# Charging.net
KiCad netlist of a schematic drawn in Altium Designer
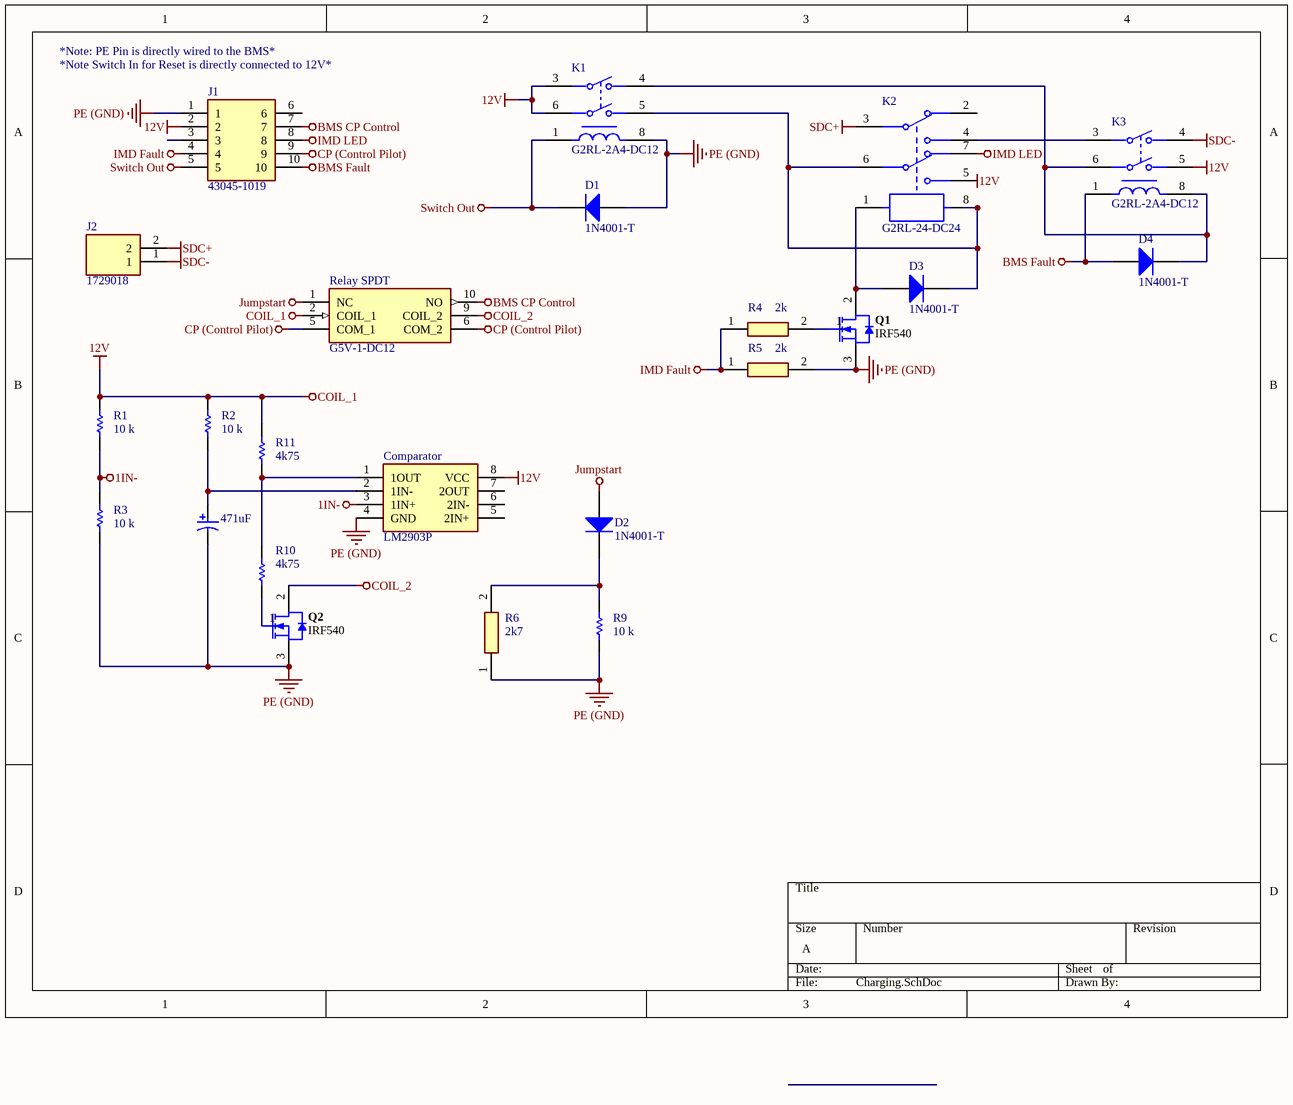
[diagram p0: Charging.SchDoc]

(export (version "E")
  (design (tool "Eeschema 10.0.6"))
  (components
    (comp (ref "471uF")
      (value "ECA-1JHG471")
      (footprint "CAPPR65-500-2000X1250X2200")
      (fields (field (name "MANUFACTURER") "Panasonic"))
      (libsource (lib "Altium Content Vault") (part "CAP-P-2"))
    )
    (comp (ref "Comparator")
      (value "LM2903P")
      (footprint "SamacSys:DIP794W53P254L959H508Q8N")
      (description "Integrated Circuit")
      (fields (field (name "MOUSER PART NUMBER") "595-LM2903P"))
      (libsource (lib "*") (part "LM2903P"))
    )
    (comp (ref "D1")
      (value "1N4001-T")
      (footprint "DIOD-DO-41-P-2_V")
      (description "1.0 A Rectifier, 15 pF, 50 V, -65 to 150 degC, 2-Pin DO-41 Plastic, RoHS, Tape and Reel")
      (fields (field (name "MANUFACTURER") "Diodes Inc"))
      (libsource (lib "Altium Content Vault") (part "DIOD-D-A1K2-2"))
    )
    (comp (ref "D2")
      (value "1N4001-T")
      (footprint "DIOD-DO-41-P-2_V")
      (description "1.0 A Rectifier, 15 pF, 50 V, -65 to 150 degC, 2-Pin DO-41 Plastic, RoHS, Tape and Reel")
      (fields (field (name "MANUFACTURER") "Diodes Inc"))
      (libsource (lib "Altium Content Vault") (part "DIOD-D-A1K2-2"))
    )
    (comp (ref "D3")
      (value "1N4001-T")
      (footprint "DIOD-DO-41-P-2_V")
      (description "1.0 A Rectifier, 15 pF, 50 V, -65 to 150 degC, 2-Pin DO-41 Plastic, RoHS, Tape and Reel")
      (fields (field (name "MANUFACTURER") "Diodes Inc"))
      (libsource (lib "Altium Content Vault") (part "DIOD-D-A1K2-2"))
    )
    (comp (ref "D4")
      (value "1N4001-T")
      (footprint "DIOD-DO-41-P-2_V")
      (description "1.0 A Rectifier, 15 pF, 50 V, -65 to 150 degC, 2-Pin DO-41 Plastic, RoHS, Tape and Reel")
      (fields (field (name "MANUFACTURER") "Diodes Inc"))
      (libsource (lib "Altium Content Vault") (part "DIOD-D-A1K2-2"))
    )
    (comp (ref "J1")
      (value "43045-1019")
      (footprint "SamacSys:43045-10YY_181920")
      (description "Connector")
      (fields (field (name "MOUSER PART NUMBER") "538-43045-1019"))
      (libsource (lib "*") (part "43045-1019"))
    )
    (comp (ref "J2")
      (value "1729018")
      (footprint "SamacSys:1729018")
      (description "Connector")
      (fields (field (name "MOUSER PART NUMBER") "651-1729018"))
      (libsource (lib "*") (part "1729018"))
    )
    (comp (ref "K1")
      (value "G2RL-2A4-DC12")
      (footprint "FP-G2RL-2A4-DC12-MFG")
      (description "RELAY GEN PURPOSE DPST 8A 12V")
      (libsource (lib "Altium Content Vault") (part "dfb52caf01785165d8ace8a37fe0b79"))
    )
    (comp (ref "K2")
      (value "G2RL-24-DC24")
      (footprint "OMRON-G2RL-24_V")
      (fields (field (name "MANUFACTURER") "Omron"))
      (libsource (lib "Altium Content Vault") (part "RELAY-DPDT-8_C"))
    )
    (comp (ref "K3")
      (value "G2RL-2A4-DC12")
      (footprint "FP-G2RL-2A4-DC12-MFG")
      (description "RELAY GEN PURPOSE DPST 8A 12V")
      (libsource (lib "Altium Content Vault") (part "dfb52caf01785165d8ace8a37fe0b79"))
    )
    (comp (ref "Q1")
      (value "IRF540")
      (footprint "VISH-TO-220AB-3_A")
      (description "Power MOSFET, 100 VDS, -55 to 175 degC, 3-Pin TO-220AB, RoHS, Tube")
      (fields (field (name "MANUFACTURER") "Vishay"))
      (libsource (lib "Altium Content Vault") (part "NEMOS-GDS-3"))
    )
    (comp (ref "Q2")
      (value "IRF540")
      (footprint "VISH-TO-220AB-3_A")
      (description "Power MOSFET, 100 VDS, -55 to 175 degC, 3-Pin TO-220AB, RoHS, Tube")
      (fields (field (name "MANUFACTURER") "Vishay"))
      (libsource (lib "Altium Content Vault") (part "NEMOS-GDS-3"))
    )
    (comp (ref "R1")
      (value "MFR-25FBF52-1K")
      (footprint "RESA60-630X240")
      (description "Axial Resistor, 1 KOhm, +/- 1%, 250 mW, -55 to 155 degC, 2-Pin THD, RoHS, Bulk")
      (fields (field (name "TOLERANCE") "1%") (field (name "RESISTANCE") "10 k"))
      (libsource (lib "Altium Content Vault") (part "RES-2"))
    )
    (comp (ref "R2")
      (value "MFR-25FBF52-1K")
      (footprint "RESA60-630X240")
      (description "Axial Resistor, 1 KOhm, +/- 1%, 250 mW, -55 to 155 degC, 2-Pin THD, RoHS, Bulk")
      (fields (field (name "TOLERANCE") "1%") (field (name "RESISTANCE") "10 k"))
      (libsource (lib "Altium Content Vault") (part "RES-2"))
    )
    (comp (ref "R3")
      (value "MFR-25FBF52-1K")
      (footprint "RESA60-630X240")
      (description "Axial Resistor, 1 KOhm, +/- 1%, 250 mW, -55 to 155 degC, 2-Pin THD, RoHS, Bulk")
      (fields (field (name "TOLERANCE") "1%") (field (name "RESISTANCE") "10 k"))
      (libsource (lib "Altium Content Vault") (part "RES-2"))
    )
    (comp (ref "R4")
      (value "MFR-25FBF52-2K")
      (footprint "SamacSys:RESAD1590W60L630D240")
      (description "Resistor")
      (fields (field (name "RESISTANCE") "2k"))
      (libsource (lib "*") (part "MFR-25FBF52-2K"))
    )
    (comp (ref "R5")
      (value "MFR-25FBF52-2K")
      (footprint "SamacSys:RESAD1590W60L630D240")
      (description "Resistor")
      (fields (field (name "RESISTANCE") "2k"))
      (libsource (lib "*") (part "MFR-25FBF52-2K"))
    )
    (comp (ref "R6")
      (value "2.7k")
      (footprint "SamacSys:RESAD1590W60L630D240")
      (description "Resistor")
      (fields
        (field (name "MANUFACTURER_PART_NUMBER") "CFR-25JB-52-2K7")
        (field (name "MOUSER PART NUMBER") "603-CFR-25JB-52-2K7")
        (field (name "RESISTANCE") "2k7")
      )
      (libsource (lib "*") (part "CFR-25JB-52-2K7"))
    )
    (comp (ref "R9")
      (value "MFR-25FBF52-1K")
      (footprint "RESA60-630X240")
      (description "Axial Resistor, 1 KOhm, +/- 1%, 250 mW, -55 to 155 degC, 2-Pin THD, RoHS, Bulk")
      (fields (field (name "TOLERANCE") "1%") (field (name "RESISTANCE") "10 k"))
      (libsource (lib "Altium Content Vault") (part "RES-2"))
    )
    (comp (ref "R10")
      (value "4.75 k")
      (footprint "RESA60-630X240")
      (description "Axial Resistor, 4.75 KOhm, +/- 1%, 0.25 W, -55 to 155 degC, 2-Pin THD, RoHS, Bulk")
      (fields (field (name "TOLERANCE") "10%") (field (name "RESISTANCE") "4k75"))
      (libsource (lib "Altium Content Vault") (part "RES-2"))
    )
    (comp (ref "R11")
      (value "4.75 k")
      (footprint "RESA60-630X240")
      (description "Axial Resistor, 4.75 KOhm, +/- 1%, 0.25 W, -55 to 155 degC, 2-Pin THD, RoHS, Bulk")
      (fields (field (name "TOLERANCE") "10%") (field (name "RESISTANCE") "4k75"))
      (libsource (lib "Altium Content Vault") (part "RES-2"))
    )
    (comp (ref "Relay SPDT")
      (value "G5V-1-DC12")
      (footprint "SamacSys:G5V1DC12")
      (description "Relay or Contactor")
      (fields (field (name "MOUSER PART NUMBER") "653-G5V-1-DC12"))
      (libsource (lib "*") (part "G5V-1-DC12"))
    )
  )
  (nets
    (net (code "1") (name "1IN-") (class "Default")
      (node (ref "Comparator") (pin "3") (pinfunction "1IN+_3") (pintype "passive"))
      (node (ref "R1") (pin "1") (pinfunction "1_1") (pintype "passive"))
      (node (ref "R3") (pin "2") (pinfunction "2_2") (pintype "passive"))
    )
    (net (code "2") (name "12V") (class "Default")
      (node (ref "Comparator") (pin "8") (pinfunction "VCC_8") (pintype "passive"))
      (node (ref "J1") (pin "2") (pinfunction "2_2") (pintype "passive"))
      (node (ref "K1") (pin "3") (pinfunction "3_3") (pintype "passive"))
      (node (ref "K1") (pin "6") (pinfunction "6_6") (pintype "passive"))
      (node (ref "K3") (pin "5") (pinfunction "5_5") (pintype "passive"))
      (node (ref "R1") (pin "2") (pinfunction "2_2") (pintype "passive"))
      (node (ref "R11") (pin "2") (pinfunction "2_2") (pintype "passive"))
      (node (ref "R2") (pin "2") (pinfunction "2_2") (pintype "passive"))
      (node (ref "Relay SPDT") (pin "2") (pinfunction "COIL_1_2") (pintype "input"))
    )
    (net (code "3") (name "BMS CP Control") (class "Default")
      (node (ref "J1") (pin "7") (pinfunction "7_7") (pintype "passive"))
      (node (ref "Relay SPDT") (pin "10") (pinfunction "NO_10") (pintype "output"))
    )
    (net (code "4") (name "BMS Fault") (class "Default")
      (node (ref "D4") (pin "1") (pinfunction "A_1") (pintype "passive"))
      (node (ref "J1") (pin "10") (pinfunction "10_10") (pintype "passive"))
      (node (ref "K3") (pin "1") (pinfunction "1_1") (pintype "passive"))
    )
    (net (code "5") (name "COIL_2") (class "Default")
      (node (ref "Q2") (pin "2") (pinfunction "D_2") (pintype "passive"))
      (node (ref "Relay SPDT") (pin "9") (pinfunction "COIL_2_9") (pintype "power_in"))
    )
    (net (code "6") (name "CP (Control Pilot)") (class "Default")
      (node (ref "J1") (pin "9") (pinfunction "9_9") (pintype "passive"))
      (node (ref "Relay SPDT") (pin "5") (pinfunction "COM_1_5") (pintype "passive"))
      (node (ref "Relay SPDT") (pin "6") (pinfunction "COM_2_6") (pintype "passive"))
    )
    (net (code "7") (name "IMD Fault") (class "Default")
      (node (ref "J1") (pin "4") (pinfunction "4_4") (pintype "passive"))
      (node (ref "R4") (pin "1") (pinfunction "1_1") (pintype "passive"))
      (node (ref "R5") (pin "1") (pinfunction "1_1") (pintype "passive"))
    )
    (net (code "8") (name "IMD LED") (class "Default")
      (node (ref "J1") (pin "8") (pinfunction "8_8") (pintype "passive"))
      (node (ref "K2") (pin "7") (pinfunction "7_7") (pintype "passive"))
    )
    (net (code "9") (name "Jumpstart") (class "Default")
      (node (ref "D2") (pin "1") (pinfunction "A_1") (pintype "passive"))
      (node (ref "Relay SPDT") (pin "1") (pinfunction "NC_1") (pintype "passive"))
    )
    (net (code "10") (name "Net-(Comparator-1IN-)") (class "Default")
      (node (ref "471uF") (pin "1") (pinfunction "1_1") (pintype "passive"))
      (node (ref "Comparator") (pin "2") (pinfunction "1IN-_2") (pintype "passive"))
      (node (ref "R2") (pin "1") (pinfunction "1_1") (pintype "passive"))
    )
    (net (code "11") (name "Net-(Comparator-1OUT)") (class "Default")
      (node (ref "Comparator") (pin "1") (pinfunction "1OUT_1") (pintype "passive"))
      (node (ref "R10") (pin "1") (pinfunction "1_1") (pintype "passive"))
      (node (ref "R11") (pin "1") (pinfunction "1_1") (pintype "passive"))
    )
    (net (code "12") (name "Net-(D2-K)") (class "Default")
      (node (ref "D2") (pin "2") (pinfunction "K_2") (pintype "passive"))
      (node (ref "R6") (pin "2") (pinfunction "2_2") (pintype "passive"))
      (node (ref "R9") (pin "2") (pinfunction "2_2") (pintype "passive"))
    )
    (net (code "13") (name "Net-(D3-A)") (class "Default")
      (node (ref "D3") (pin "1") (pinfunction "A_1") (pintype "passive"))
      (node (ref "K2") (pin "1") (pinfunction "1_1") (pintype "passive"))
      (node (ref "Q1") (pin "2") (pinfunction "D_2") (pintype "passive"))
    )
    (net (code "14") (name "Net-(D3-K)") (class "Default")
      (node (ref "D3") (pin "2") (pinfunction "K_2") (pintype "passive"))
      (node (ref "K1") (pin "5") (pinfunction "5_5") (pintype "passive"))
      (node (ref "K2") (pin "6") (pinfunction "6_6") (pintype "passive"))
      (node (ref "K2") (pin "8") (pinfunction "8_8") (pintype "passive"))
    )
    (net (code "15") (name "Net-(D4-K)") (class "Default")
      (node (ref "D4") (pin "2") (pinfunction "K_2") (pintype "passive"))
      (node (ref "K1") (pin "4") (pinfunction "4_4") (pintype "passive"))
      (node (ref "K3") (pin "6") (pinfunction "6_6") (pintype "passive"))
      (node (ref "K3") (pin "8") (pinfunction "8_8") (pintype "passive"))
    )
    (net (code "16") (name "Net-(K2-Pad4)") (class "Default")
      (node (ref "K2") (pin "4") (pinfunction "4_4") (pintype "passive"))
      (node (ref "K3") (pin "3") (pinfunction "3_3") (pintype "passive"))
    )
    (net (code "17") (name "Net-(Q1-G)") (class "Default")
      (node (ref "Q1") (pin "1") (pinfunction "G_1") (pintype "passive"))
      (node (ref "R4") (pin "2") (pinfunction "2_2") (pintype "passive"))
    )
    (net (code "18") (name "Net-(Q2-G)") (class "Default")
      (node (ref "Q2") (pin "1") (pinfunction "G_1") (pintype "passive"))
      (node (ref "R10") (pin "2") (pinfunction "2_2") (pintype "passive"))
    )
    (net (code "19") (name "PE (GND)") (class "Default")
      (node (ref "471uF") (pin "2") (pinfunction "2_2") (pintype "passive"))
      (node (ref "Comparator") (pin "4") (pinfunction "GND_4") (pintype "passive"))
      (node (ref "D1") (pin "1") (pinfunction "A_1") (pintype "passive"))
      (node (ref "J1") (pin "1") (pinfunction "1_1") (pintype "passive"))
      (node (ref "K1") (pin "8") (pinfunction "8_8") (pintype "passive"))
      (node (ref "Q1") (pin "3") (pinfunction "S_3") (pintype "passive"))
      (node (ref "Q2") (pin "3") (pinfunction "S_3") (pintype "passive"))
      (node (ref "R3") (pin "1") (pinfunction "1_1") (pintype "passive"))
      (node (ref "R5") (pin "2") (pinfunction "2_2") (pintype "passive"))
      (node (ref "R6") (pin "1") (pinfunction "1_1") (pintype "passive"))
      (node (ref "R9") (pin "1") (pinfunction "1_1") (pintype "passive"))
    )
    (net (code "20") (name "SDC+") (class "Default")
      (node (ref "J2") (pin "2") (pinfunction "2_2") (pintype "passive"))
      (node (ref "K2") (pin "3") (pinfunction "3_3") (pintype "passive"))
    )
    (net (code "21") (name "SDC-") (class "Default")
      (node (ref "J2") (pin "1") (pinfunction "1_1") (pintype "passive"))
      (node (ref "K3") (pin "4") (pinfunction "4_4") (pintype "passive"))
    )
    (net (code "22") (name "Switch Out") (class "Default")
      (node (ref "D1") (pin "2") (pinfunction "K_2") (pintype "passive"))
      (node (ref "J1") (pin "5") (pinfunction "5_5") (pintype "passive"))
      (node (ref "K1") (pin "1") (pinfunction "1_1") (pintype "passive"))
    )
    (net (code "23") (name "unconnected-(Comparator-2IN+-Pad5)") (class "Default")
      (node (ref "Comparator") (pin "5") (pinfunction "2IN+_5") (pintype "passive"))
    )
    (net (code "24") (name "unconnected-(Comparator-2IN--Pad6)") (class "Default")
      (node (ref "Comparator") (pin "6") (pinfunction "2IN-_6") (pintype "passive"))
    )
    (net (code "25") (name "unconnected-(Comparator-2OUT-Pad7)") (class "Default")
      (node (ref "Comparator") (pin "7") (pinfunction "2OUT_7") (pintype "passive"))
    )
    (net (code "26") (name "unconnected-(J1-Pad3)") (class "Default")
      (node (ref "J1") (pin "3") (pinfunction "3_3") (pintype "passive"))
    )
    (net (code "27") (name "unconnected-(J1-Pad6)") (class "Default")
      (node (ref "J1") (pin "6") (pinfunction "6_6") (pintype "passive"))
    )
    (net (code "28") (name "unconnected-(K2-Pad2)") (class "Default")
      (node (ref "K2") (pin "2") (pinfunction "2_2") (pintype "passive"))
    )
    (net (code "29") (name "unconnected-(K2-Pad5)") (class "Default")
      (node (ref "K2") (pin "5") (pinfunction "5_5") (pintype "passive"))
    )
  )
)
